# Sheet2.net
KiCad netlist of a schematic drawn in Altium Designer
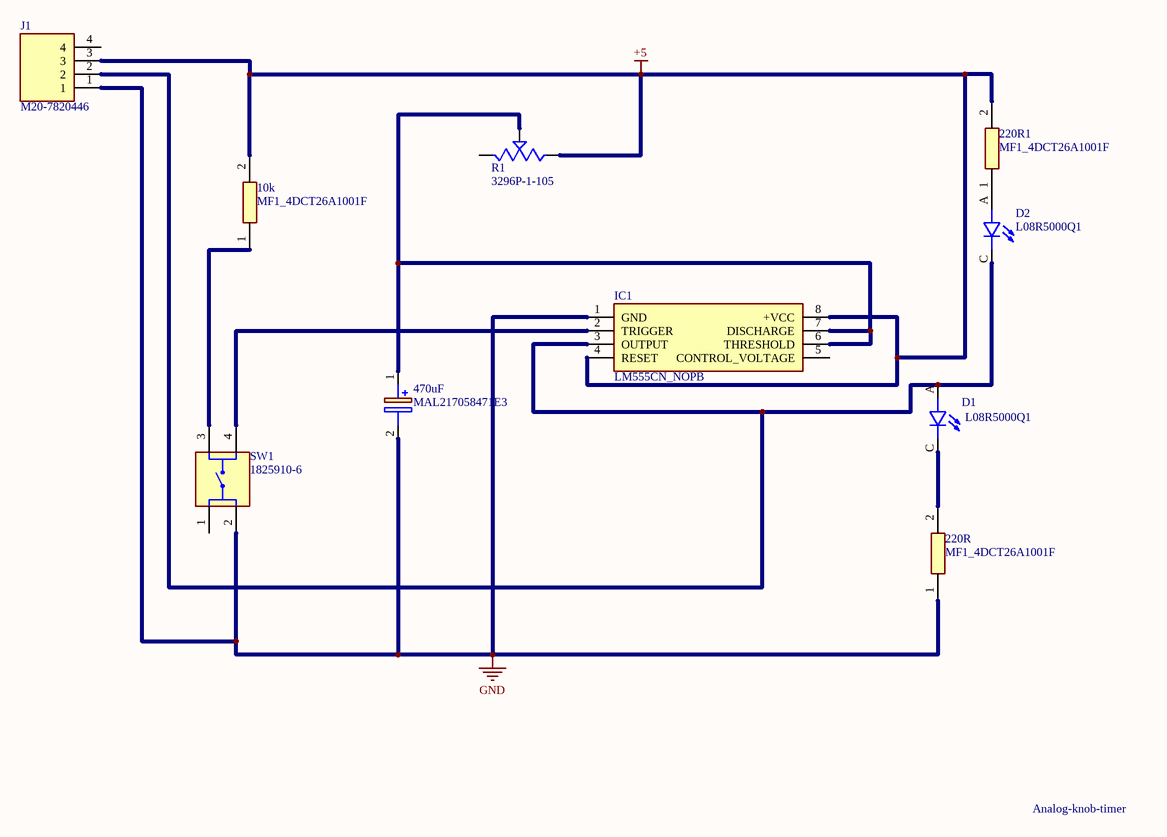
[diagram p0: Sheet2.SchDoc]

(export (version "E")
  (design (tool "Eeschema 10.0.6"))
  (components
    (comp (ref "10k")
      (value "MF1_4DCT26A1001F")
      (footprint "SamacSys:RESAD1630W60L710D230")
      (description "Resistor")
      (fields
        (field (name "MANUFACTURER_PART_NUMBER") "MF1/4DCT26A1001F")
        (field (name "MOUSER PART NUMBER") "660-MF1/4DCT26A1001F")
      )
      (libsource (lib "SamacSys") (part "MF1_4DCT26A1001F"))
    )
    (comp (ref "220R")
      (value "MF1_4DCT26A1001F")
      (footprint "SamacSys:RESAD1630W60L710D230")
      (description "Resistor")
      (fields
        (field (name "MANUFACTURER_PART_NUMBER") "MF1/4DCT26A1001F")
        (field (name "MOUSER PART NUMBER") "660-MF1/4DCT26A1001F")
      )
      (libsource (lib "SamacSys") (part "MF1_4DCT26A1001F"))
    )
    (comp (ref "220R1")
      (value "MF1_4DCT26A1001F")
      (footprint "SamacSys:RESAD1630W60L710D230")
      (description "Resistor")
      (fields
        (field (name "MANUFACTURER_PART_NUMBER") "MF1/4DCT26A1001F")
        (field (name "MOUSER PART NUMBER") "660-MF1/4DCT26A1001F")
      )
      (libsource (lib "SamacSys") (part "MF1_4DCT26A1001F"))
    )
    (comp (ref "470uF")
      (value "MAL217058471E3")
      (footprint "SamacSys:CAPPRD500W60D1300H2700")
      (description "Capacitor Polarised")
      (fields (field (name "MOUSER PART NUMBER") "594-MAL217058471E3"))
      (libsource (lib "*") (part "MAL217058471E3"))
    )
    (comp (ref "D1")
      (value "L08R5000Q1")
      (footprint "LEDRD254W57D500H1070")
      (fields (field (name "MF") "LED Technology"))
      (libsource (lib "L08R5000Q1") (part "L08R5000Q1"))
    )
    (comp (ref "D2")
      (value "L08R5000Q1")
      (footprint "LEDRD254W57D500H1070")
      (fields (field (name "MF") "LED Technology"))
      (libsource (lib "L08R5000Q1") (part "L08R5000Q1"))
    )
    (comp (ref "IC1")
      (value "LM555CN_NOPB")
      (footprint "SamacSys:DIP794W53P254L959H508Q8N")
      (description "Integrated Circuit")
      (fields
        (field (name "MANUFACTURER_PART_NUMBER") "LM555CN/NOPB")
        (field (name "MOUSER PART NUMBER") "926-LM555CN/NOPB")
      )
      (libsource (lib "SamacSys") (part "LM555CN_NOPB"))
    )
    (comp (ref "J1")
      (value "M20-7820446")
      (footprint "SamacSys:RHDR4W70P0X254_1X4_1056X250X865P")
      (description "Connector")
      (fields (field (name "MOUSER PART NUMBER") "855-M20-7820446"))
      (libsource (lib "SamacSys") (part "M20-7820446"))
    )
    (comp (ref "R1")
      (value "3296P-1-105")
      (footprint "TRIM_3296P-1-105")
      (description "1 kOhms 0.5W, 1/2W PC Pins Through Hole Trimmer Potentiometer Cermet 25 Turn Side Adjustment")
      (fields (field (name "MP") "altium_native_batch"))
      (libsource (lib "3296P-1-105") (part "3296P-1-105"))
    )
    (comp (ref "SW1")
      (value "1825910-6")
      (footprint "SW_1825910-6-4")
      (description "Switch Push Button OFF (ON) SPST Round Button 0.05A 24VDC Momentary Contact PC Pins Thru-Hole")
      (fields (field (name "MF") "TE Connectivity") (field (name "DIGI-KEY_PART_NUMBER") "450-1650-ND"))
      (libsource (lib "1825910-6") (part "1825910-6"))
    )
  )
  (nets
    (net (code "1") (name "+5") (class "Default")
      (node (ref "10k") (pin "2") (pinfunction "2_2") (pintype "passive"))
      (node (ref "220R1") (pin "2") (pinfunction "2_2") (pintype "passive"))
      (node (ref "IC1") (pin "4") (pinfunction "RESET_4") (pintype "passive"))
      (node (ref "IC1") (pin "8") (pinfunction "+VCC_8") (pintype "passive"))
      (node (ref "J1") (pin "3") (pinfunction "3_3") (pintype "passive"))
      (node (ref "R1") (pin "1") (pinfunction "CCW_1") (pintype "passive"))
    )
    (net (code "2") (name "GND") (class "Default")
      (node (ref "220R") (pin "1") (pinfunction "1_1") (pintype "passive"))
      (node (ref "470uF") (pin "2") (pinfunction "-_2") (pintype "passive"))
      (node (ref "IC1") (pin "1") (pinfunction "GND_1") (pintype "passive"))
      (node (ref "J1") (pin "1") (pinfunction "1_1") (pintype "passive"))
      (node (ref "SW1") (pin "2") (pinfunction "2_2") (pintype "passive"))
    )
    (net (code "3") (name "Net-(10k-Pad1)") (class "Default")
      (node (ref "10k") (pin "1") (pinfunction "1_1") (pintype "passive"))
      (node (ref "SW1") (pin "3") (pinfunction "3_3") (pintype "passive"))
    )
    (net (code "4") (name "Net-(220R-Pad2)") (class "Default")
      (node (ref "220R") (pin "2") (pinfunction "2_2") (pintype "passive"))
      (node (ref "D1") (pin "C") (pinfunction "C_C") (pintype "passive"))
    )
    (net (code "5") (name "Net-(220R1-Pad1)") (class "Default")
      (node (ref "220R1") (pin "1") (pinfunction "1_1") (pintype "passive"))
      (node (ref "D2") (pin "A") (pinfunction "A_A") (pintype "passive"))
    )
    (net (code "6") (name "Net-(470uF-+)") (class "Default")
      (node (ref "470uF") (pin "1") (pinfunction "+_1") (pintype "passive"))
      (node (ref "IC1") (pin "6") (pinfunction "THRESHOLD_6") (pintype "passive"))
      (node (ref "IC1") (pin "7") (pinfunction "DISCHARGE_7") (pintype "passive"))
      (node (ref "R1") (pin "2") (pinfunction "WIPER_2") (pintype "passive"))
    )
    (net (code "7") (name "Net-(IC1-OUTPUT)") (class "Default")
      (node (ref "D1") (pin "A") (pinfunction "A_A") (pintype "passive"))
      (node (ref "D2") (pin "C") (pinfunction "C_C") (pintype "passive"))
      (node (ref "IC1") (pin "3") (pinfunction "OUTPUT_3") (pintype "passive"))
      (node (ref "J1") (pin "2") (pinfunction "2_2") (pintype "passive"))
    )
    (net (code "8") (name "Net-(IC1-TRIGGER)") (class "Default")
      (node (ref "IC1") (pin "2") (pinfunction "TRIGGER_2") (pintype "passive"))
      (node (ref "SW1") (pin "4") (pinfunction "4_4") (pintype "passive"))
    )
    (net (code "9") (name "unconnected-(IC1-CONTROL_VOLTAGE-Pad5)") (class "Default")
      (node (ref "IC1") (pin "5") (pinfunction "CONTROL_VOLTAGE_5") (pintype "passive"))
    )
    (net (code "10") (name "unconnected-(J1-Pad4)") (class "Default")
      (node (ref "J1") (pin "4") (pinfunction "4_4") (pintype "passive"))
    )
    (net (code "11") (name "unconnected-(R1-CW-Pad3)") (class "Default")
      (node (ref "R1") (pin "3") (pinfunction "CW_3") (pintype "passive"))
    )
    (net (code "12") (name "unconnected-(SW1-Pad1)") (class "Default")
      (node (ref "SW1") (pin "1") (pinfunction "1_1") (pintype "passive"))
    )
  )
)
